# MonthCalendar_TouchPlate_v0_8.net
KiCad netlist of a schematic drawn in EAGLE
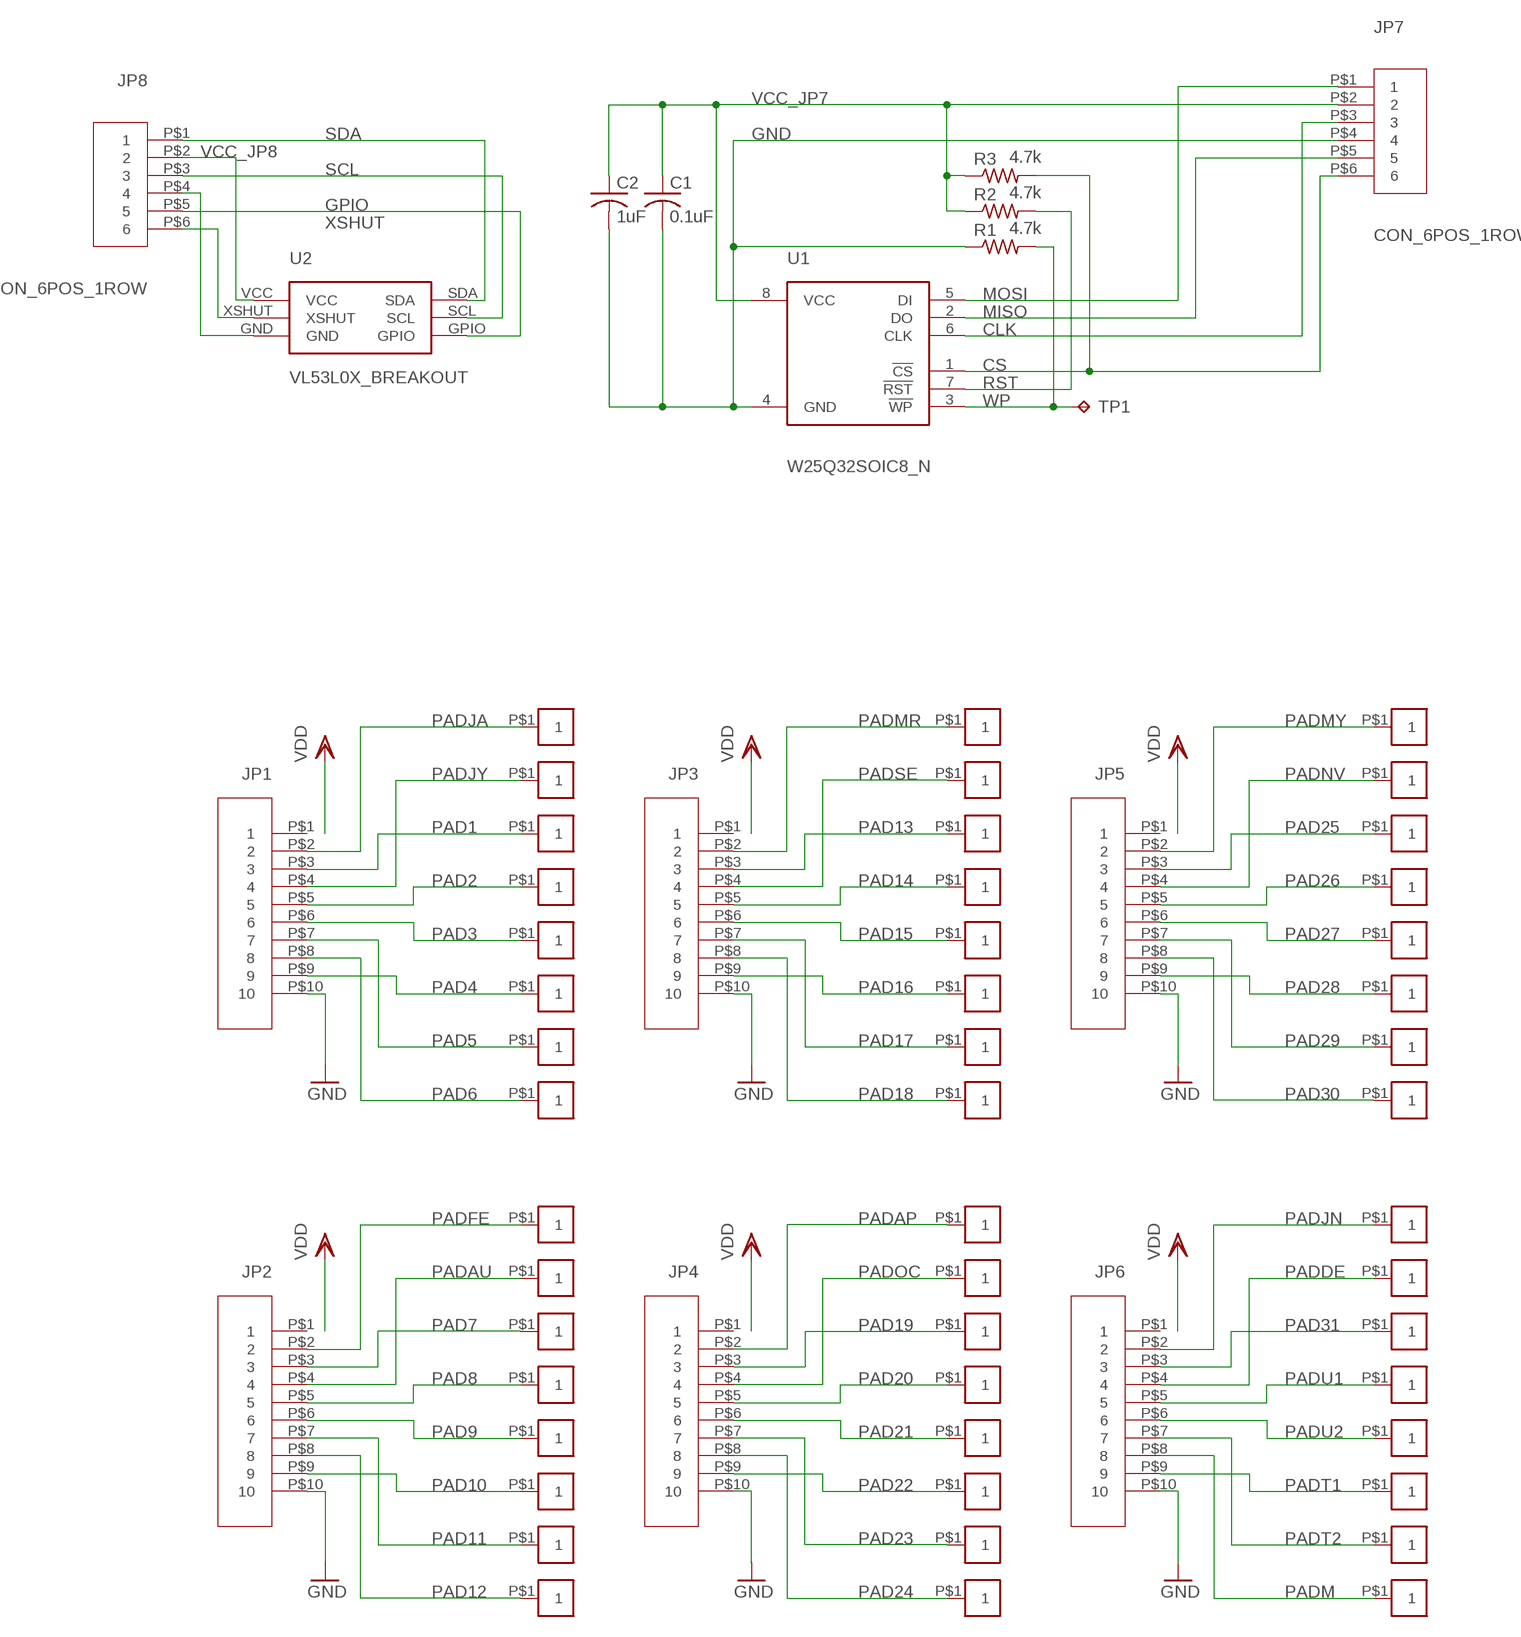
[diagram p0: schematic, sheet 1]

(export (version "E")
  (design (tool "Eeschema 10.0.6"))
  (components
    (comp (ref "C1")
      (value "0.1uF")
      (footprint "eagle-import:C0603")
      (libsource (lib "eagle-import") (part "C-USC0603"))
    )
    (comp (ref "C2")
      (value "1uF")
      (footprint "eagle-import:C0603")
      (libsource (lib "eagle-import") (part "C-USC0603"))
    )
    (comp (ref "JP1")
      (value "CON_10POS_1ROWHARWIN_M50-3141045_N")
      (footprint "eagle-import:CON_RECPT_10P_1R_SMD_HARWIN_M50-3141045_NARROW")
      (libsource (lib "eagle-import") (part "CON_10POS_1ROWHARWIN_M50-3141045_N"))
    )
    (comp (ref "JP2")
      (value "CON_10POS_1ROWHARWIN_M50-3141045_N")
      (footprint "eagle-import:CON_RECPT_10P_1R_SMD_HARWIN_M50-3141045_NARROW")
      (libsource (lib "eagle-import") (part "CON_10POS_1ROWHARWIN_M50-3141045_N"))
    )
    (comp (ref "JP3")
      (value "CON_10POS_1ROWHARWIN_M50-3141045_N")
      (footprint "eagle-import:CON_RECPT_10P_1R_SMD_HARWIN_M50-3141045_NARROW")
      (libsource (lib "eagle-import") (part "CON_10POS_1ROWHARWIN_M50-3141045_N"))
    )
    (comp (ref "JP4")
      (value "CON_10POS_1ROWHARWIN_M50-3141045_N")
      (footprint "eagle-import:CON_RECPT_10P_1R_SMD_HARWIN_M50-3141045_NARROW")
      (libsource (lib "eagle-import") (part "CON_10POS_1ROWHARWIN_M50-3141045_N"))
    )
    (comp (ref "JP5")
      (value "CON_10POS_1ROWHARWIN_M50-3141045_N")
      (footprint "eagle-import:CON_RECPT_10P_1R_SMD_HARWIN_M50-3141045_NARROW")
      (libsource (lib "eagle-import") (part "CON_10POS_1ROWHARWIN_M50-3141045_N"))
    )
    (comp (ref "JP6")
      (value "CON_10POS_1ROWHARWIN_M50-3141045_N")
      (footprint "eagle-import:CON_RECPT_10P_1R_SMD_HARWIN_M50-3141045_NARROW")
      (libsource (lib "eagle-import") (part "CON_10POS_1ROWHARWIN_M50-3141045_N"))
    )
    (comp (ref "JP7")
      (value "CON_6POS_1ROW")
      (footprint "eagle-import:CON_RECPT_6P_1R_SMD_HARWIN_M50-3141045_NARROW")
      (libsource (lib "eagle-import") (part "CON_6POS_1ROW"))
    )
    (comp (ref "JP8")
      (value "CON_6POS_1ROW")
      (footprint "eagle-import:CON_RECPT_6P_1R_SMD_HARWIN_M50-3141045_NARROW")
      (libsource (lib "eagle-import") (part "CON_6POS_1ROW"))
    )
    (comp (ref "R1")
      (value "4.7k")
      (footprint "eagle-import:R0603")
      (libsource (lib "eagle-import") (part "R-US_R0603"))
    )
    (comp (ref "R2")
      (value "4.7k")
      (footprint "eagle-import:R0603")
      (libsource (lib "eagle-import") (part "R-US_R0603"))
    )
    (comp (ref "R3")
      (value "4.7k")
      (footprint "eagle-import:R0603")
      (libsource (lib "eagle-import") (part "R-US_R0603"))
    )
    (comp (ref "TP1")
      (value "TPTP20SQ")
      (footprint "eagle-import:TP20SQ")
      (libsource (lib "eagle-import") (part "TPTP20SQ"))
    )
    (comp (ref "U$1")
      (value "PAD_CAPACITIVETOUCHV4")
      (footprint "eagle-import:PAD_CAPACITIVETOUCH_4")
      (libsource (lib "eagle-import") (part "PAD_CAPACITIVETOUCHV4"))
    )
    (comp (ref "U$2")
      (value "PAD_CAPACITIVETOUCHV4")
      (footprint "eagle-import:PAD_CAPACITIVETOUCH_4")
      (libsource (lib "eagle-import") (part "PAD_CAPACITIVETOUCHV4"))
    )
    (comp (ref "U$3")
      (value "PAD_CAPACITIVETOUCHV4")
      (footprint "eagle-import:PAD_CAPACITIVETOUCH_4")
      (libsource (lib "eagle-import") (part "PAD_CAPACITIVETOUCHV4"))
    )
    (comp (ref "U$4")
      (value "PAD_CAPACITIVETOUCHV4")
      (footprint "eagle-import:PAD_CAPACITIVETOUCH_4")
      (libsource (lib "eagle-import") (part "PAD_CAPACITIVETOUCHV4"))
    )
    (comp (ref "U$5")
      (value "PAD_CAPACITIVETOUCHV4")
      (footprint "eagle-import:PAD_CAPACITIVETOUCH_4")
      (libsource (lib "eagle-import") (part "PAD_CAPACITIVETOUCHV4"))
    )
    (comp (ref "U$6")
      (value "PAD_CAPACITIVETOUCHV4")
      (footprint "eagle-import:PAD_CAPACITIVETOUCH_4")
      (libsource (lib "eagle-import") (part "PAD_CAPACITIVETOUCHV4"))
    )
    (comp (ref "U$7")
      (value "PAD_CAPACITIVETOUCHV4")
      (footprint "eagle-import:PAD_CAPACITIVETOUCH_4")
      (libsource (lib "eagle-import") (part "PAD_CAPACITIVETOUCHV4"))
    )
    (comp (ref "U$8")
      (value "PAD_CAPACITIVETOUCHV4")
      (footprint "eagle-import:PAD_CAPACITIVETOUCH_4")
      (libsource (lib "eagle-import") (part "PAD_CAPACITIVETOUCHV4"))
    )
    (comp (ref "U$9")
      (value "PAD_CAPACITIVETOUCHV4")
      (footprint "eagle-import:PAD_CAPACITIVETOUCH_4")
      (libsource (lib "eagle-import") (part "PAD_CAPACITIVETOUCHV4"))
    )
    (comp (ref "U$10")
      (value "PAD_CAPACITIVETOUCHV4")
      (footprint "eagle-import:PAD_CAPACITIVETOUCH_4")
      (libsource (lib "eagle-import") (part "PAD_CAPACITIVETOUCHV4"))
    )
    (comp (ref "U$11")
      (value "PAD_CAPACITIVETOUCHV4")
      (footprint "eagle-import:PAD_CAPACITIVETOUCH_4")
      (libsource (lib "eagle-import") (part "PAD_CAPACITIVETOUCHV4"))
    )
    (comp (ref "U$12")
      (value "PAD_CAPACITIVETOUCHV4")
      (footprint "eagle-import:PAD_CAPACITIVETOUCH_4")
      (libsource (lib "eagle-import") (part "PAD_CAPACITIVETOUCHV4"))
    )
    (comp (ref "U$13")
      (value "PAD_CAPACITIVETOUCHV4")
      (footprint "eagle-import:PAD_CAPACITIVETOUCH_4")
      (libsource (lib "eagle-import") (part "PAD_CAPACITIVETOUCHV4"))
    )
    (comp (ref "U$14")
      (value "PAD_CAPACITIVETOUCHV4")
      (footprint "eagle-import:PAD_CAPACITIVETOUCH_4")
      (libsource (lib "eagle-import") (part "PAD_CAPACITIVETOUCHV4"))
    )
    (comp (ref "U$15")
      (value "PAD_CAPACITIVETOUCHV4")
      (footprint "eagle-import:PAD_CAPACITIVETOUCH_4")
      (libsource (lib "eagle-import") (part "PAD_CAPACITIVETOUCHV4"))
    )
    (comp (ref "U$16")
      (value "PAD_CAPACITIVETOUCHV4")
      (footprint "eagle-import:PAD_CAPACITIVETOUCH_4")
      (libsource (lib "eagle-import") (part "PAD_CAPACITIVETOUCHV4"))
    )
    (comp (ref "U$17")
      (value "PAD_CAPACITIVETOUCHV4")
      (footprint "eagle-import:PAD_CAPACITIVETOUCH_4")
      (libsource (lib "eagle-import") (part "PAD_CAPACITIVETOUCHV4"))
    )
    (comp (ref "U$18")
      (value "PAD_CAPACITIVETOUCHV4")
      (footprint "eagle-import:PAD_CAPACITIVETOUCH_4")
      (libsource (lib "eagle-import") (part "PAD_CAPACITIVETOUCHV4"))
    )
    (comp (ref "U$19")
      (value "PAD_CAPACITIVETOUCHV4")
      (footprint "eagle-import:PAD_CAPACITIVETOUCH_4")
      (libsource (lib "eagle-import") (part "PAD_CAPACITIVETOUCHV4"))
    )
    (comp (ref "U$20")
      (value "PAD_CAPACITIVETOUCHV4")
      (footprint "eagle-import:PAD_CAPACITIVETOUCH_4")
      (libsource (lib "eagle-import") (part "PAD_CAPACITIVETOUCHV4"))
    )
    (comp (ref "U$21")
      (value "PAD_CAPACITIVETOUCHV4")
      (footprint "eagle-import:PAD_CAPACITIVETOUCH_4")
      (libsource (lib "eagle-import") (part "PAD_CAPACITIVETOUCHV4"))
    )
    (comp (ref "U$22")
      (value "PAD_CAPACITIVETOUCHV4")
      (footprint "eagle-import:PAD_CAPACITIVETOUCH_4")
      (libsource (lib "eagle-import") (part "PAD_CAPACITIVETOUCHV4"))
    )
    (comp (ref "U$23")
      (value "PAD_CAPACITIVETOUCHV4")
      (footprint "eagle-import:PAD_CAPACITIVETOUCH_4")
      (libsource (lib "eagle-import") (part "PAD_CAPACITIVETOUCHV4"))
    )
    (comp (ref "U$24")
      (value "PAD_CAPACITIVETOUCHV4")
      (footprint "eagle-import:PAD_CAPACITIVETOUCH_4")
      (libsource (lib "eagle-import") (part "PAD_CAPACITIVETOUCHV4"))
    )
    (comp (ref "U$25")
      (value "PAD_CAPACITIVETOUCHV4")
      (footprint "eagle-import:PAD_CAPACITIVETOUCH_4")
      (libsource (lib "eagle-import") (part "PAD_CAPACITIVETOUCHV4"))
    )
    (comp (ref "U$26")
      (value "PAD_CAPACITIVETOUCHV4")
      (footprint "eagle-import:PAD_CAPACITIVETOUCH_4")
      (libsource (lib "eagle-import") (part "PAD_CAPACITIVETOUCHV4"))
    )
    (comp (ref "U$27")
      (value "PAD_CAPACITIVETOUCHV4")
      (footprint "eagle-import:PAD_CAPACITIVETOUCH_4")
      (libsource (lib "eagle-import") (part "PAD_CAPACITIVETOUCHV4"))
    )
    (comp (ref "U$28")
      (value "PAD_CAPACITIVETOUCHV4")
      (footprint "eagle-import:PAD_CAPACITIVETOUCH_4")
      (libsource (lib "eagle-import") (part "PAD_CAPACITIVETOUCHV4"))
    )
    (comp (ref "U$29")
      (value "PAD_CAPACITIVETOUCHV4")
      (footprint "eagle-import:PAD_CAPACITIVETOUCH_4")
      (libsource (lib "eagle-import") (part "PAD_CAPACITIVETOUCHV4"))
    )
    (comp (ref "U$30")
      (value "PAD_CAPACITIVETOUCHV4")
      (footprint "eagle-import:PAD_CAPACITIVETOUCH_4")
      (libsource (lib "eagle-import") (part "PAD_CAPACITIVETOUCHV4"))
    )
    (comp (ref "U$31")
      (value "PAD_CAPACITIVETOUCHV4")
      (footprint "eagle-import:PAD_CAPACITIVETOUCH_4")
      (libsource (lib "eagle-import") (part "PAD_CAPACITIVETOUCHV4"))
    )
    (comp (ref "U$32")
      (value "PAD_CAPACITIVETOUCHV4")
      (footprint "eagle-import:PAD_CAPACITIVETOUCH_4")
      (libsource (lib "eagle-import") (part "PAD_CAPACITIVETOUCHV4"))
    )
    (comp (ref "U$33")
      (value "PAD_CAPACITIVETOUCHV4")
      (footprint "eagle-import:PAD_CAPACITIVETOUCH_4")
      (libsource (lib "eagle-import") (part "PAD_CAPACITIVETOUCHV4"))
    )
    (comp (ref "U$34")
      (value "PAD_CAPACITIVETOUCHV4")
      (footprint "eagle-import:PAD_CAPACITIVETOUCH_4")
      (libsource (lib "eagle-import") (part "PAD_CAPACITIVETOUCHV4"))
    )
    (comp (ref "U$35")
      (value "PAD_CAPACITIVETOUCHV4")
      (footprint "eagle-import:PAD_CAPACITIVETOUCH_4")
      (libsource (lib "eagle-import") (part "PAD_CAPACITIVETOUCHV4"))
    )
    (comp (ref "U$36")
      (value "PAD_CAPACITIVETOUCHV4")
      (footprint "eagle-import:PAD_CAPACITIVETOUCH_4")
      (libsource (lib "eagle-import") (part "PAD_CAPACITIVETOUCHV4"))
    )
    (comp (ref "U$37")
      (value "PAD_CAPACITIVETOUCHV4")
      (footprint "eagle-import:PAD_CAPACITIVETOUCH_4")
      (libsource (lib "eagle-import") (part "PAD_CAPACITIVETOUCHV4"))
    )
    (comp (ref "U$38")
      (value "PAD_CAPACITIVETOUCHV4")
      (footprint "eagle-import:PAD_CAPACITIVETOUCH_4")
      (libsource (lib "eagle-import") (part "PAD_CAPACITIVETOUCHV4"))
    )
    (comp (ref "U$39")
      (value "PAD_CAPACITIVETOUCHV4")
      (footprint "eagle-import:PAD_CAPACITIVETOUCH_4")
      (libsource (lib "eagle-import") (part "PAD_CAPACITIVETOUCHV4"))
    )
    (comp (ref "U$40")
      (value "PAD_CAPACITIVETOUCHV4")
      (footprint "eagle-import:PAD_CAPACITIVETOUCH_4")
      (libsource (lib "eagle-import") (part "PAD_CAPACITIVETOUCHV4"))
    )
    (comp (ref "U$41")
      (value "PAD_CAPACITIVETOUCHV4")
      (footprint "eagle-import:PAD_CAPACITIVETOUCH_4")
      (libsource (lib "eagle-import") (part "PAD_CAPACITIVETOUCHV4"))
    )
    (comp (ref "U$42")
      (value "PAD_CAPACITIVETOUCHV4")
      (footprint "eagle-import:PAD_CAPACITIVETOUCH_4")
      (libsource (lib "eagle-import") (part "PAD_CAPACITIVETOUCHV4"))
    )
    (comp (ref "U$43")
      (value "PAD_CAPACITIVETOUCHV4")
      (footprint "eagle-import:PAD_CAPACITIVETOUCH_4")
      (libsource (lib "eagle-import") (part "PAD_CAPACITIVETOUCHV4"))
    )
    (comp (ref "U$44")
      (value "PAD_CAPACITIVETOUCHV4")
      (footprint "eagle-import:PAD_CAPACITIVETOUCH_4")
      (libsource (lib "eagle-import") (part "PAD_CAPACITIVETOUCHV4"))
    )
    (comp (ref "U$45")
      (value "PAD_CAPACITIVETOUCHV4")
      (footprint "eagle-import:PAD_CAPACITIVETOUCH_4")
      (libsource (lib "eagle-import") (part "PAD_CAPACITIVETOUCHV4"))
    )
    (comp (ref "U$46")
      (value "PAD_CAPACITIVETOUCHV4")
      (footprint "eagle-import:PAD_CAPACITIVETOUCH_4")
      (libsource (lib "eagle-import") (part "PAD_CAPACITIVETOUCHV4"))
    )
    (comp (ref "U$47")
      (value "PAD_CAPACITIVETOUCHV4")
      (footprint "eagle-import:PAD_CAPACITIVETOUCH_4")
      (libsource (lib "eagle-import") (part "PAD_CAPACITIVETOUCHV4"))
    )
    (comp (ref "U$48")
      (value "PAD_CAPACITIVETOUCHV4")
      (footprint "eagle-import:PAD_CAPACITIVETOUCH_4")
      (libsource (lib "eagle-import") (part "PAD_CAPACITIVETOUCHV4"))
    )
    (comp (ref "U1")
      (value "W25Q32SOIC8_N")
      (footprint "eagle-import:SOIC-8_NARROW")
      (libsource (lib "eagle-import") (part "W25Q32SOIC8_N"))
    )
    (comp (ref "U2")
      (value "VL53L0X_BREAKOUT")
      (footprint "eagle-import:VL53L0X_BREAKOUT_THROUGHPCB")
      (libsource (lib "eagle-import") (part "VL53L0X_BREAKOUT"))
    )
  )
  (nets
    (net (code "1") (name "/CLK") (class "Default")
      (node (ref "JP7") (pin "P$3") (pinfunction "3_P$3") (pintype "bidirectional"))
      (node (ref "U1") (pin "6") (pinfunction "CLK_6") (pintype "input"))
    )
    (net (code "2") (name "/CS") (class "Default")
      (node (ref "JP7") (pin "P$6") (pinfunction "6_P$6") (pintype "bidirectional"))
      (node (ref "R3") (pin "2") (pinfunction "2_2") (pintype "passive"))
      (node (ref "U1") (pin "1") (pinfunction "~{CS}_1") (pintype "input"))
    )
    (net (code "3") (name "/GPIO") (class "Default")
      (node (ref "JP8") (pin "P$5") (pinfunction "5_P$5") (pintype "bidirectional"))
      (node (ref "U2") (pin "GPIO") (pinfunction "GPIO_GPIO") (pintype "bidirectional"))
    )
    (net (code "4") (name "/MISO") (class "Default")
      (node (ref "JP7") (pin "P$5") (pinfunction "5_P$5") (pintype "bidirectional"))
      (node (ref "U1") (pin "2") (pinfunction "DO_2") (pintype "output"))
    )
    (net (code "5") (name "/MOSI") (class "Default")
      (node (ref "JP7") (pin "P$1") (pinfunction "1_P$1") (pintype "bidirectional"))
      (node (ref "U1") (pin "5") (pinfunction "DI_5") (pintype "input"))
    )
    (net (code "6") (name "/PAD1") (class "Default")
      (node (ref "JP1") (pin "P$3") (pinfunction "3_P$3") (pintype "bidirectional"))
      (node (ref "U$3") (pin "P$1") (pinfunction "1_P$1") (pintype "bidirectional"))
    )
    (net (code "7") (name "/PAD2") (class "Default")
      (node (ref "JP1") (pin "P$5") (pinfunction "5_P$5") (pintype "bidirectional"))
      (node (ref "U$4") (pin "P$1") (pinfunction "1_P$1") (pintype "bidirectional"))
    )
    (net (code "8") (name "/PAD3") (class "Default")
      (node (ref "JP1") (pin "P$6") (pinfunction "6_P$6") (pintype "bidirectional"))
      (node (ref "U$5") (pin "P$1") (pinfunction "1_P$1") (pintype "bidirectional"))
    )
    (net (code "9") (name "/PAD4") (class "Default")
      (node (ref "JP1") (pin "P$9") (pinfunction "9_P$9") (pintype "bidirectional"))
      (node (ref "U$6") (pin "P$1") (pinfunction "1_P$1") (pintype "bidirectional"))
    )
    (net (code "10") (name "/PAD5") (class "Default")
      (node (ref "JP1") (pin "P$7") (pinfunction "7_P$7") (pintype "bidirectional"))
      (node (ref "U$7") (pin "P$1") (pinfunction "1_P$1") (pintype "bidirectional"))
    )
    (net (code "11") (name "/PAD6") (class "Default")
      (node (ref "JP1") (pin "P$8") (pinfunction "8_P$8") (pintype "bidirectional"))
      (node (ref "U$8") (pin "P$1") (pinfunction "1_P$1") (pintype "bidirectional"))
    )
    (net (code "12") (name "/PAD7") (class "Default")
      (node (ref "JP2") (pin "P$3") (pinfunction "3_P$3") (pintype "bidirectional"))
      (node (ref "U$11") (pin "P$1") (pinfunction "1_P$1") (pintype "bidirectional"))
    )
    (net (code "13") (name "/PAD8") (class "Default")
      (node (ref "JP2") (pin "P$5") (pinfunction "5_P$5") (pintype "bidirectional"))
      (node (ref "U$12") (pin "P$1") (pinfunction "1_P$1") (pintype "bidirectional"))
    )
    (net (code "14") (name "/PAD9") (class "Default")
      (node (ref "JP2") (pin "P$6") (pinfunction "6_P$6") (pintype "bidirectional"))
      (node (ref "U$13") (pin "P$1") (pinfunction "1_P$1") (pintype "bidirectional"))
    )
    (net (code "15") (name "/PAD10") (class "Default")
      (node (ref "JP2") (pin "P$9") (pinfunction "9_P$9") (pintype "bidirectional"))
      (node (ref "U$14") (pin "P$1") (pinfunction "1_P$1") (pintype "bidirectional"))
    )
    (net (code "16") (name "/PAD11") (class "Default")
      (node (ref "JP2") (pin "P$7") (pinfunction "7_P$7") (pintype "bidirectional"))
      (node (ref "U$15") (pin "P$1") (pinfunction "1_P$1") (pintype "bidirectional"))
    )
    (net (code "17") (name "/PAD12") (class "Default")
      (node (ref "JP2") (pin "P$8") (pinfunction "8_P$8") (pintype "bidirectional"))
      (node (ref "U$16") (pin "P$1") (pinfunction "1_P$1") (pintype "bidirectional"))
    )
    (net (code "18") (name "/PAD13") (class "Default")
      (node (ref "JP3") (pin "P$3") (pinfunction "3_P$3") (pintype "bidirectional"))
      (node (ref "U$19") (pin "P$1") (pinfunction "1_P$1") (pintype "bidirectional"))
    )
    (net (code "19") (name "/PAD14") (class "Default")
      (node (ref "JP3") (pin "P$5") (pinfunction "5_P$5") (pintype "bidirectional"))
      (node (ref "U$20") (pin "P$1") (pinfunction "1_P$1") (pintype "bidirectional"))
    )
    (net (code "20") (name "/PAD15") (class "Default")
      (node (ref "JP3") (pin "P$6") (pinfunction "6_P$6") (pintype "bidirectional"))
      (node (ref "U$21") (pin "P$1") (pinfunction "1_P$1") (pintype "bidirectional"))
    )
    (net (code "21") (name "/PAD16") (class "Default")
      (node (ref "JP3") (pin "P$9") (pinfunction "9_P$9") (pintype "bidirectional"))
      (node (ref "U$22") (pin "P$1") (pinfunction "1_P$1") (pintype "bidirectional"))
    )
    (net (code "22") (name "/PAD17") (class "Default")
      (node (ref "JP3") (pin "P$7") (pinfunction "7_P$7") (pintype "bidirectional"))
      (node (ref "U$23") (pin "P$1") (pinfunction "1_P$1") (pintype "bidirectional"))
    )
    (net (code "23") (name "/PAD18") (class "Default")
      (node (ref "JP3") (pin "P$8") (pinfunction "8_P$8") (pintype "bidirectional"))
      (node (ref "U$24") (pin "P$1") (pinfunction "1_P$1") (pintype "bidirectional"))
    )
    (net (code "24") (name "/PAD19") (class "Default")
      (node (ref "JP4") (pin "P$3") (pinfunction "3_P$3") (pintype "bidirectional"))
      (node (ref "U$27") (pin "P$1") (pinfunction "1_P$1") (pintype "bidirectional"))
    )
    (net (code "25") (name "/PAD20") (class "Default")
      (node (ref "JP4") (pin "P$5") (pinfunction "5_P$5") (pintype "bidirectional"))
      (node (ref "U$28") (pin "P$1") (pinfunction "1_P$1") (pintype "bidirectional"))
    )
    (net (code "26") (name "/PAD21") (class "Default")
      (node (ref "JP4") (pin "P$6") (pinfunction "6_P$6") (pintype "bidirectional"))
      (node (ref "U$29") (pin "P$1") (pinfunction "1_P$1") (pintype "bidirectional"))
    )
    (net (code "27") (name "/PAD22") (class "Default")
      (node (ref "JP4") (pin "P$9") (pinfunction "9_P$9") (pintype "bidirectional"))
      (node (ref "U$30") (pin "P$1") (pinfunction "1_P$1") (pintype "bidirectional"))
    )
    (net (code "28") (name "/PAD23") (class "Default")
      (node (ref "JP4") (pin "P$7") (pinfunction "7_P$7") (pintype "bidirectional"))
      (node (ref "U$31") (pin "P$1") (pinfunction "1_P$1") (pintype "bidirectional"))
    )
    (net (code "29") (name "/PAD24") (class "Default")
      (node (ref "JP4") (pin "P$8") (pinfunction "8_P$8") (pintype "bidirectional"))
      (node (ref "U$32") (pin "P$1") (pinfunction "1_P$1") (pintype "bidirectional"))
    )
    (net (code "30") (name "/PAD25") (class "Default")
      (node (ref "JP5") (pin "P$3") (pinfunction "3_P$3") (pintype "bidirectional"))
      (node (ref "U$35") (pin "P$1") (pinfunction "1_P$1") (pintype "bidirectional"))
    )
    (net (code "31") (name "/PAD26") (class "Default")
      (node (ref "JP5") (pin "P$5") (pinfunction "5_P$5") (pintype "bidirectional"))
      (node (ref "U$36") (pin "P$1") (pinfunction "1_P$1") (pintype "bidirectional"))
    )
    (net (code "32") (name "/PAD27") (class "Default")
      (node (ref "JP5") (pin "P$6") (pinfunction "6_P$6") (pintype "bidirectional"))
      (node (ref "U$37") (pin "P$1") (pinfunction "1_P$1") (pintype "bidirectional"))
    )
    (net (code "33") (name "/PAD28") (class "Default")
      (node (ref "JP5") (pin "P$9") (pinfunction "9_P$9") (pintype "bidirectional"))
      (node (ref "U$38") (pin "P$1") (pinfunction "1_P$1") (pintype "bidirectional"))
    )
    (net (code "34") (name "/PAD29") (class "Default")
      (node (ref "JP5") (pin "P$7") (pinfunction "7_P$7") (pintype "bidirectional"))
      (node (ref "U$39") (pin "P$1") (pinfunction "1_P$1") (pintype "bidirectional"))
    )
    (net (code "35") (name "/PAD30") (class "Default")
      (node (ref "JP5") (pin "P$8") (pinfunction "8_P$8") (pintype "bidirectional"))
      (node (ref "U$40") (pin "P$1") (pinfunction "1_P$1") (pintype "bidirectional"))
    )
    (net (code "36") (name "/PAD31") (class "Default")
      (node (ref "JP6") (pin "P$3") (pinfunction "3_P$3") (pintype "bidirectional"))
      (node (ref "U$43") (pin "P$1") (pinfunction "1_P$1") (pintype "bidirectional"))
    )
    (net (code "37") (name "/PADAP") (class "Default")
      (node (ref "JP4") (pin "P$2") (pinfunction "2_P$2") (pintype "bidirectional"))
      (node (ref "U$25") (pin "P$1") (pinfunction "1_P$1") (pintype "bidirectional"))
    )
    (net (code "38") (name "/PADAU") (class "Default")
      (node (ref "JP2") (pin "P$4") (pinfunction "4_P$4") (pintype "bidirectional"))
      (node (ref "U$10") (pin "P$1") (pinfunction "1_P$1") (pintype "bidirectional"))
    )
    (net (code "39") (name "/PADDE") (class "Default")
      (node (ref "JP6") (pin "P$4") (pinfunction "4_P$4") (pintype "bidirectional"))
      (node (ref "U$42") (pin "P$1") (pinfunction "1_P$1") (pintype "bidirectional"))
    )
    (net (code "40") (name "/PADFE") (class "Default")
      (node (ref "JP2") (pin "P$2") (pinfunction "2_P$2") (pintype "bidirectional"))
      (node (ref "U$9") (pin "P$1") (pinfunction "1_P$1") (pintype "bidirectional"))
    )
    (net (code "41") (name "/PADJA") (class "Default")
      (node (ref "JP1") (pin "P$2") (pinfunction "2_P$2") (pintype "bidirectional"))
      (node (ref "U$1") (pin "P$1") (pinfunction "1_P$1") (pintype "bidirectional"))
    )
    (net (code "42") (name "/PADJN") (class "Default")
      (node (ref "JP6") (pin "P$2") (pinfunction "2_P$2") (pintype "bidirectional"))
      (node (ref "U$41") (pin "P$1") (pinfunction "1_P$1") (pintype "bidirectional"))
    )
    (net (code "43") (name "/PADJY") (class "Default")
      (node (ref "JP1") (pin "P$4") (pinfunction "4_P$4") (pintype "bidirectional"))
      (node (ref "U$2") (pin "P$1") (pinfunction "1_P$1") (pintype "bidirectional"))
    )
    (net (code "44") (name "/PADM") (class "Default")
      (node (ref "JP6") (pin "P$8") (pinfunction "8_P$8") (pintype "bidirectional"))
      (node (ref "U$48") (pin "P$1") (pinfunction "1_P$1") (pintype "bidirectional"))
    )
    (net (code "45") (name "/PADMR") (class "Default")
      (node (ref "JP3") (pin "P$2") (pinfunction "2_P$2") (pintype "bidirectional"))
      (node (ref "U$17") (pin "P$1") (pinfunction "1_P$1") (pintype "bidirectional"))
    )
    (net (code "46") (name "/PADMY") (class "Default")
      (node (ref "JP5") (pin "P$2") (pinfunction "2_P$2") (pintype "bidirectional"))
      (node (ref "U$33") (pin "P$1") (pinfunction "1_P$1") (pintype "bidirectional"))
    )
    (net (code "47") (name "/PADNV") (class "Default")
      (node (ref "JP5") (pin "P$4") (pinfunction "4_P$4") (pintype "bidirectional"))
      (node (ref "U$34") (pin "P$1") (pinfunction "1_P$1") (pintype "bidirectional"))
    )
    (net (code "48") (name "/PADOC") (class "Default")
      (node (ref "JP4") (pin "P$4") (pinfunction "4_P$4") (pintype "bidirectional"))
      (node (ref "U$26") (pin "P$1") (pinfunction "1_P$1") (pintype "bidirectional"))
    )
    (net (code "49") (name "/PADSE") (class "Default")
      (node (ref "JP3") (pin "P$4") (pinfunction "4_P$4") (pintype "bidirectional"))
      (node (ref "U$18") (pin "P$1") (pinfunction "1_P$1") (pintype "bidirectional"))
    )
    (net (code "50") (name "/PADT1") (class "Default")
      (node (ref "JP6") (pin "P$9") (pinfunction "9_P$9") (pintype "bidirectional"))
      (node (ref "U$46") (pin "P$1") (pinfunction "1_P$1") (pintype "bidirectional"))
    )
    (net (code "51") (name "/PADT2") (class "Default")
      (node (ref "JP6") (pin "P$7") (pinfunction "7_P$7") (pintype "bidirectional"))
      (node (ref "U$47") (pin "P$1") (pinfunction "1_P$1") (pintype "bidirectional"))
    )
    (net (code "52") (name "/PADU1") (class "Default")
      (node (ref "JP6") (pin "P$5") (pinfunction "5_P$5") (pintype "bidirectional"))
      (node (ref "U$44") (pin "P$1") (pinfunction "1_P$1") (pintype "bidirectional"))
    )
    (net (code "53") (name "/PADU2") (class "Default")
      (node (ref "JP6") (pin "P$6") (pinfunction "6_P$6") (pintype "bidirectional"))
      (node (ref "U$45") (pin "P$1") (pinfunction "1_P$1") (pintype "bidirectional"))
    )
    (net (code "54") (name "/RST") (class "Default")
      (node (ref "R2") (pin "2") (pinfunction "2_2") (pintype "passive"))
      (node (ref "U1") (pin "7") (pinfunction "~{RST}_7") (pintype "input"))
    )
    (net (code "55") (name "/SCL") (class "Default")
      (node (ref "JP8") (pin "P$3") (pinfunction "3_P$3") (pintype "bidirectional"))
      (node (ref "U2") (pin "SCL") (pinfunction "SCL_SCL") (pintype "bidirectional"))
    )
    (net (code "56") (name "/SDA") (class "Default")
      (node (ref "JP8") (pin "P$1") (pinfunction "1_P$1") (pintype "bidirectional"))
      (node (ref "U2") (pin "SDA") (pinfunction "SDA_SDA") (pintype "bidirectional"))
    )
    (net (code "57") (name "/VCC_JP7") (class "Default")
      (node (ref "C1") (pin "1") (pinfunction "1_1") (pintype "passive"))
      (node (ref "C2") (pin "1") (pinfunction "1_1") (pintype "passive"))
      (node (ref "JP7") (pin "P$2") (pinfunction "2_P$2") (pintype "bidirectional"))
      (node (ref "R2") (pin "1") (pinfunction "1_1") (pintype "passive"))
      (node (ref "R3") (pin "1") (pinfunction "1_1") (pintype "passive"))
      (node (ref "U1") (pin "8") (pinfunction "VCC_8") (pintype "power_in"))
    )
    (net (code "58") (name "/VCC_JP8") (class "Default")
      (node (ref "JP8") (pin "P$2") (pinfunction "2_P$2") (pintype "bidirectional"))
      (node (ref "U2") (pin "VCC") (pinfunction "VCC_VCC") (pintype "power_in"))
    )
    (net (code "59") (name "/WP") (class "Default")
      (node (ref "R1") (pin "2") (pinfunction "2_2") (pintype "passive"))
      (node (ref "TP1") (pin "TP") (pinfunction "TP_TP") (pintype "input"))
      (node (ref "U1") (pin "3") (pinfunction "~{WP}_3") (pintype "input"))
    )
    (net (code "60") (name "/XSHUT") (class "Default")
      (node (ref "JP8") (pin "P$6") (pinfunction "6_P$6") (pintype "bidirectional"))
      (node (ref "U2") (pin "XSHUT") (pinfunction "XSHUT_XSHUT") (pintype "input"))
    )
    (net (code "61") (name "GND") (class "Default")
      (node (ref "C1") (pin "2") (pinfunction "2_2") (pintype "passive"))
      (node (ref "C2") (pin "2") (pinfunction "2_2") (pintype "passive"))
      (node (ref "JP1") (pin "P$10") (pinfunction "10_P$10") (pintype "bidirectional"))
      (node (ref "JP2") (pin "P$10") (pinfunction "10_P$10") (pintype "bidirectional"))
      (node (ref "JP3") (pin "P$10") (pinfunction "10_P$10") (pintype "bidirectional"))
      (node (ref "JP4") (pin "P$10") (pinfunction "10_P$10") (pintype "bidirectional"))
      (node (ref "JP5") (pin "P$10") (pinfunction "10_P$10") (pintype "bidirectional"))
      (node (ref "JP6") (pin "P$10") (pinfunction "10_P$10") (pintype "bidirectional"))
      (node (ref "JP7") (pin "P$4") (pinfunction "4_P$4") (pintype "bidirectional"))
      (node (ref "JP8") (pin "P$4") (pinfunction "4_P$4") (pintype "bidirectional"))
      (node (ref "R1") (pin "1") (pinfunction "1_1") (pintype "passive"))
      (node (ref "U1") (pin "4") (pinfunction "GND_4") (pintype "power_in"))
      (node (ref "U2") (pin "GND") (pinfunction "GND_GND") (pintype "power_in"))
    )
    (net (code "63") (name "unconnected-(JP1-1-PadP$1)") (class "Default")
      (node (ref "JP1") (pin "P$1") (pinfunction "1_P$1") (pintype "bidirectional"))
    )
    (net (code "64") (name "unconnected-(JP2-1-PadP$1)") (class "Default")
      (node (ref "JP2") (pin "P$1") (pinfunction "1_P$1") (pintype "bidirectional"))
    )
    (net (code "65") (name "unconnected-(JP3-1-PadP$1)") (class "Default")
      (node (ref "JP3") (pin "P$1") (pinfunction "1_P$1") (pintype "bidirectional"))
    )
    (net (code "66") (name "unconnected-(JP4-1-PadP$1)") (class "Default")
      (node (ref "JP4") (pin "P$1") (pinfunction "1_P$1") (pintype "bidirectional"))
    )
    (net (code "67") (name "unconnected-(JP5-1-PadP$1)") (class "Default")
      (node (ref "JP5") (pin "P$1") (pinfunction "1_P$1") (pintype "bidirectional"))
    )
    (net (code "68") (name "unconnected-(JP6-1-PadP$1)") (class "Default")
      (node (ref "JP6") (pin "P$1") (pinfunction "1_P$1") (pintype "bidirectional"))
    )
  )
)
